# main.net
KiCad netlist of a schematic drawn in EAGLE
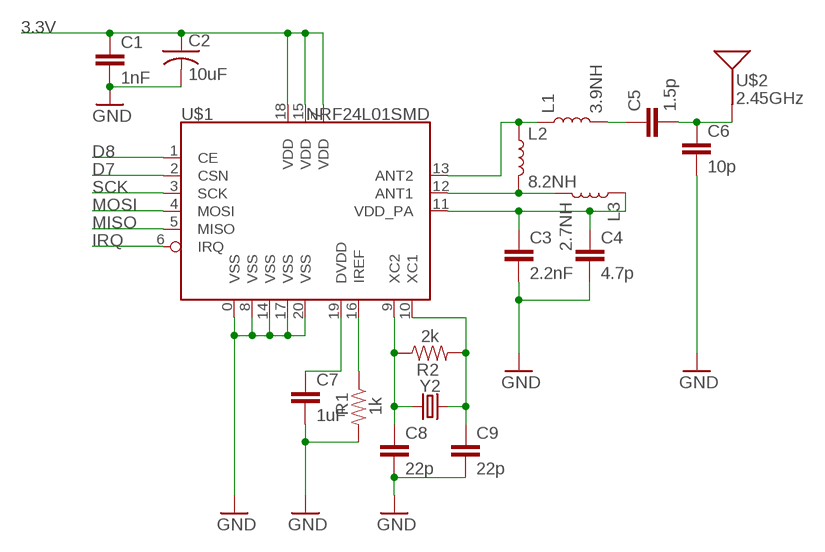
[diagram p0: schematic, sheet 1]

(export (version "E")
  (design (tool "Eeschema 10.0.6"))
  (components
    (comp (ref "C1")
      (value "1nF")
      (footprint "eagle-import:0805")
      (libsource (lib "eagle-import") (part "CAP0805"))
    )
    (comp (ref "C2")
      (value "10uF")
      (footprint "eagle-import:C1206")
      (libsource (lib "eagle-import") (part "C-USC1206"))
    )
    (comp (ref "C3")
      (value "2.2nF")
      (footprint "eagle-import:0805")
      (libsource (lib "eagle-import") (part "CAP0805"))
    )
    (comp (ref "C4")
      (value "4.7p")
      (footprint "eagle-import:0805")
      (libsource (lib "eagle-import") (part "CAP0805"))
    )
    (comp (ref "C5")
      (value "1.5p")
      (footprint "eagle-import:0805")
      (libsource (lib "eagle-import") (part "CAP0805"))
    )
    (comp (ref "C6")
      (value "10p")
      (footprint "eagle-import:0805")
      (libsource (lib "eagle-import") (part "CAP0805"))
    )
    (comp (ref "C7")
      (value "1uF")
      (footprint "eagle-import:0805")
      (libsource (lib "eagle-import") (part "CAP0805"))
    )
    (comp (ref "C8")
      (value "22p")
      (footprint "eagle-import:0805")
      (libsource (lib "eagle-import") (part "CAP0805"))
    )
    (comp (ref "C9")
      (value "22p")
      (footprint "eagle-import:0805")
      (libsource (lib "eagle-import") (part "CAP0805"))
    )
    (comp (ref "L1")
      (value "3.9NH")
      (footprint "eagle-import:0402")
      (libsource (lib "eagle-import") (part "INDUCTOR-0402-3.9NH"))
    )
    (comp (ref "L2")
      (value "8.2NH")
      (footprint "eagle-import:0402")
      (libsource (lib "eagle-import") (part "INDUCTOR-0402-3.9NH"))
    )
    (comp (ref "L3")
      (value "2.7NH")
      (footprint "eagle-import:0402")
      (libsource (lib "eagle-import") (part "INDUCTOR-0402-3.9NH"))
    )
    (comp (ref "R1")
      (value "1k")
      (footprint "eagle-import:0805")
      (libsource (lib "eagle-import") (part "RESISTOR0805-RES"))
    )
    (comp (ref "R2")
      (value "2k")
      (footprint "eagle-import:0805")
      (libsource (lib "eagle-import") (part "RESISTOR0805-RES"))
    )
    (comp (ref "U$1")
      (value "NRF24L01SMD")
      (footprint "eagle-import:QFN20-4X4MM")
      (libsource (lib "eagle-import") (part "NRF24L01SMD"))
    )
    (comp (ref "U$2")
      (value "2.45GHz")
      (footprint "eagle-import:ANT-2.4GHZ-6.5X2.2MM")
      (libsource (lib "eagle-import") (part "ANTENNA2.4GHZ-6.5X2.2MM"))
    )
    (comp (ref "Y2")
      (value "CRYSTALSMD-5X3.2-4PAD")
      (footprint "eagle-import:CRYSTAL-SMD-5X3.2-4PAD")
      (libsource (lib "eagle-import") (part "CRYSTALSMD-5X3.2-4PAD"))
    )
  )
  (nets
    (net (code "1") (name "/3.3V") (class "Default")
      (node (ref "C1") (pin "1") (pinfunction "1_1") (pintype "passive"))
      (node (ref "C2") (pin "1") (pinfunction "1_1") (pintype "passive"))
      (node (ref "U$1") (pin "15") (pinfunction "VDD_15") (pintype "power_in"))
      (node (ref "U$1") (pin "18") (pinfunction "VDD_18") (pintype "power_in"))
      (node (ref "U$1") (pin "7") (pinfunction "VDD_7") (pintype "power_in"))
    )
    (net (code "2") (name "/D7") (class "Default")
      (node (ref "U$1") (pin "2") (pinfunction "CSN_2") (pintype "input"))
    )
    (net (code "3") (name "/D8") (class "Default")
      (node (ref "U$1") (pin "1") (pinfunction "CE_1") (pintype "input"))
    )
    (net (code "4") (name "/IRQ") (class "Default")
      (node (ref "U$1") (pin "6") (pinfunction "IRQ_6") (pintype "output"))
    )
    (net (code "5") (name "/MISO") (class "Default")
      (node (ref "U$1") (pin "5") (pinfunction "MISO_5") (pintype "output"))
    )
    (net (code "6") (name "/MOSI") (class "Default")
      (node (ref "U$1") (pin "4") (pinfunction "MOSI_4") (pintype "input"))
    )
    (net (code "7") (name "/SCK") (class "Default")
      (node (ref "U$1") (pin "3") (pinfunction "SCK_3") (pintype "input"))
    )
    (net (code "8") (name "GND") (class "Default")
      (node (ref "C1") (pin "2") (pinfunction "2_2") (pintype "passive"))
      (node (ref "C2") (pin "2") (pinfunction "2_2") (pintype "passive"))
      (node (ref "C3") (pin "2") (pinfunction "2_2") (pintype "passive"))
      (node (ref "C4") (pin "2") (pinfunction "2_2") (pintype "passive"))
      (node (ref "C6") (pin "2") (pinfunction "2_2") (pintype "passive"))
      (node (ref "C7") (pin "2") (pinfunction "2_2") (pintype "passive"))
      (node (ref "C8") (pin "2") (pinfunction "2_2") (pintype "passive"))
      (node (ref "C9") (pin "2") (pinfunction "2_2") (pintype "passive"))
      (node (ref "R1") (pin "2") (pinfunction "2_2") (pintype "passive"))
      (node (ref "U$1") (pin "0") (pinfunction "VSS_0") (pintype "power_in"))
      (node (ref "U$1") (pin "14") (pinfunction "VSS_14") (pintype "power_in"))
      (node (ref "U$1") (pin "17") (pinfunction "VSS_17") (pintype "power_in"))
      (node (ref "U$1") (pin "20") (pinfunction "VSS_20") (pintype "power_in"))
      (node (ref "U$1") (pin "8") (pinfunction "VSS_8") (pintype "power_in"))
    )
    (net (code "9") (name "Net-(C5-Pad1)") (class "Default")
      (node (ref "C5") (pin "1") (pinfunction "1_1") (pintype "passive"))
      (node (ref "L1") (pin "2") (pinfunction "2_2") (pintype "passive"))
    )
    (net (code "10") (name "Net-(U$1-ANT1)") (class "Default")
      (node (ref "L2") (pin "2") (pinfunction "2_2") (pintype "passive"))
      (node (ref "L3") (pin "2") (pinfunction "2_2") (pintype "passive"))
      (node (ref "U$1") (pin "12") (pinfunction "ANT1_12") (pintype "output"))
    )
    (net (code "11") (name "Net-(U$1-ANT2)") (class "Default")
      (node (ref "L1") (pin "1") (pinfunction "1_1") (pintype "passive"))
      (node (ref "L2") (pin "1") (pinfunction "1_1") (pintype "passive"))
      (node (ref "U$1") (pin "13") (pinfunction "ANT2_13") (pintype "output"))
    )
    (net (code "12") (name "Net-(U$1-DVDD)") (class "Default")
      (node (ref "C7") (pin "1") (pinfunction "1_1") (pintype "passive"))
      (node (ref "U$1") (pin "19") (pinfunction "DVDD_19") (pintype "power_in"))
    )
    (net (code "13") (name "Net-(U$1-IREF)") (class "Default")
      (node (ref "R1") (pin "1") (pinfunction "1_1") (pintype "passive"))
      (node (ref "U$1") (pin "16") (pinfunction "IREF_16") (pintype "input"))
    )
    (net (code "14") (name "Net-(U$1-VDD_PA)") (class "Default")
      (node (ref "C3") (pin "1") (pinfunction "1_1") (pintype "passive"))
      (node (ref "C4") (pin "1") (pinfunction "1_1") (pintype "passive"))
      (node (ref "L3") (pin "1") (pinfunction "1_1") (pintype "passive"))
      (node (ref "U$1") (pin "11") (pinfunction "VDD_PA_11") (pintype "power_in"))
    )
    (net (code "15") (name "Net-(U$1-XC1)") (class "Default")
      (node (ref "C9") (pin "1") (pinfunction "1_1") (pintype "passive"))
      (node (ref "R2") (pin "2") (pinfunction "2_2") (pintype "passive"))
      (node (ref "U$1") (pin "10") (pinfunction "XC1_10") (pintype "input"))
      (node (ref "Y2") (pin "3") (pinfunction "2_3") (pintype "passive"))
    )
    (net (code "16") (name "Net-(U$1-XC2)") (class "Default")
      (node (ref "C8") (pin "1") (pinfunction "1_1") (pintype "passive"))
      (node (ref "R2") (pin "1") (pinfunction "1_1") (pintype "passive"))
      (node (ref "U$1") (pin "9") (pinfunction "XC2_9") (pintype "input"))
      (node (ref "Y2") (pin "1") (pinfunction "1_1") (pintype "passive"))
    )
    (net (code "17") (name "Net-(U$2-SIGNAL)") (class "Default")
      (node (ref "C5") (pin "2") (pinfunction "2_2") (pintype "passive"))
      (node (ref "C6") (pin "1") (pinfunction "1_1") (pintype "passive"))
      (node (ref "U$2") (pin "FEED") (pinfunction "SIGNAL_FEED") (pintype "bidirectional"))
    )
  )
)
